# esp32-gps-eth-v9exp.net
KiCad netlist of a schematic drawn in EAGLE
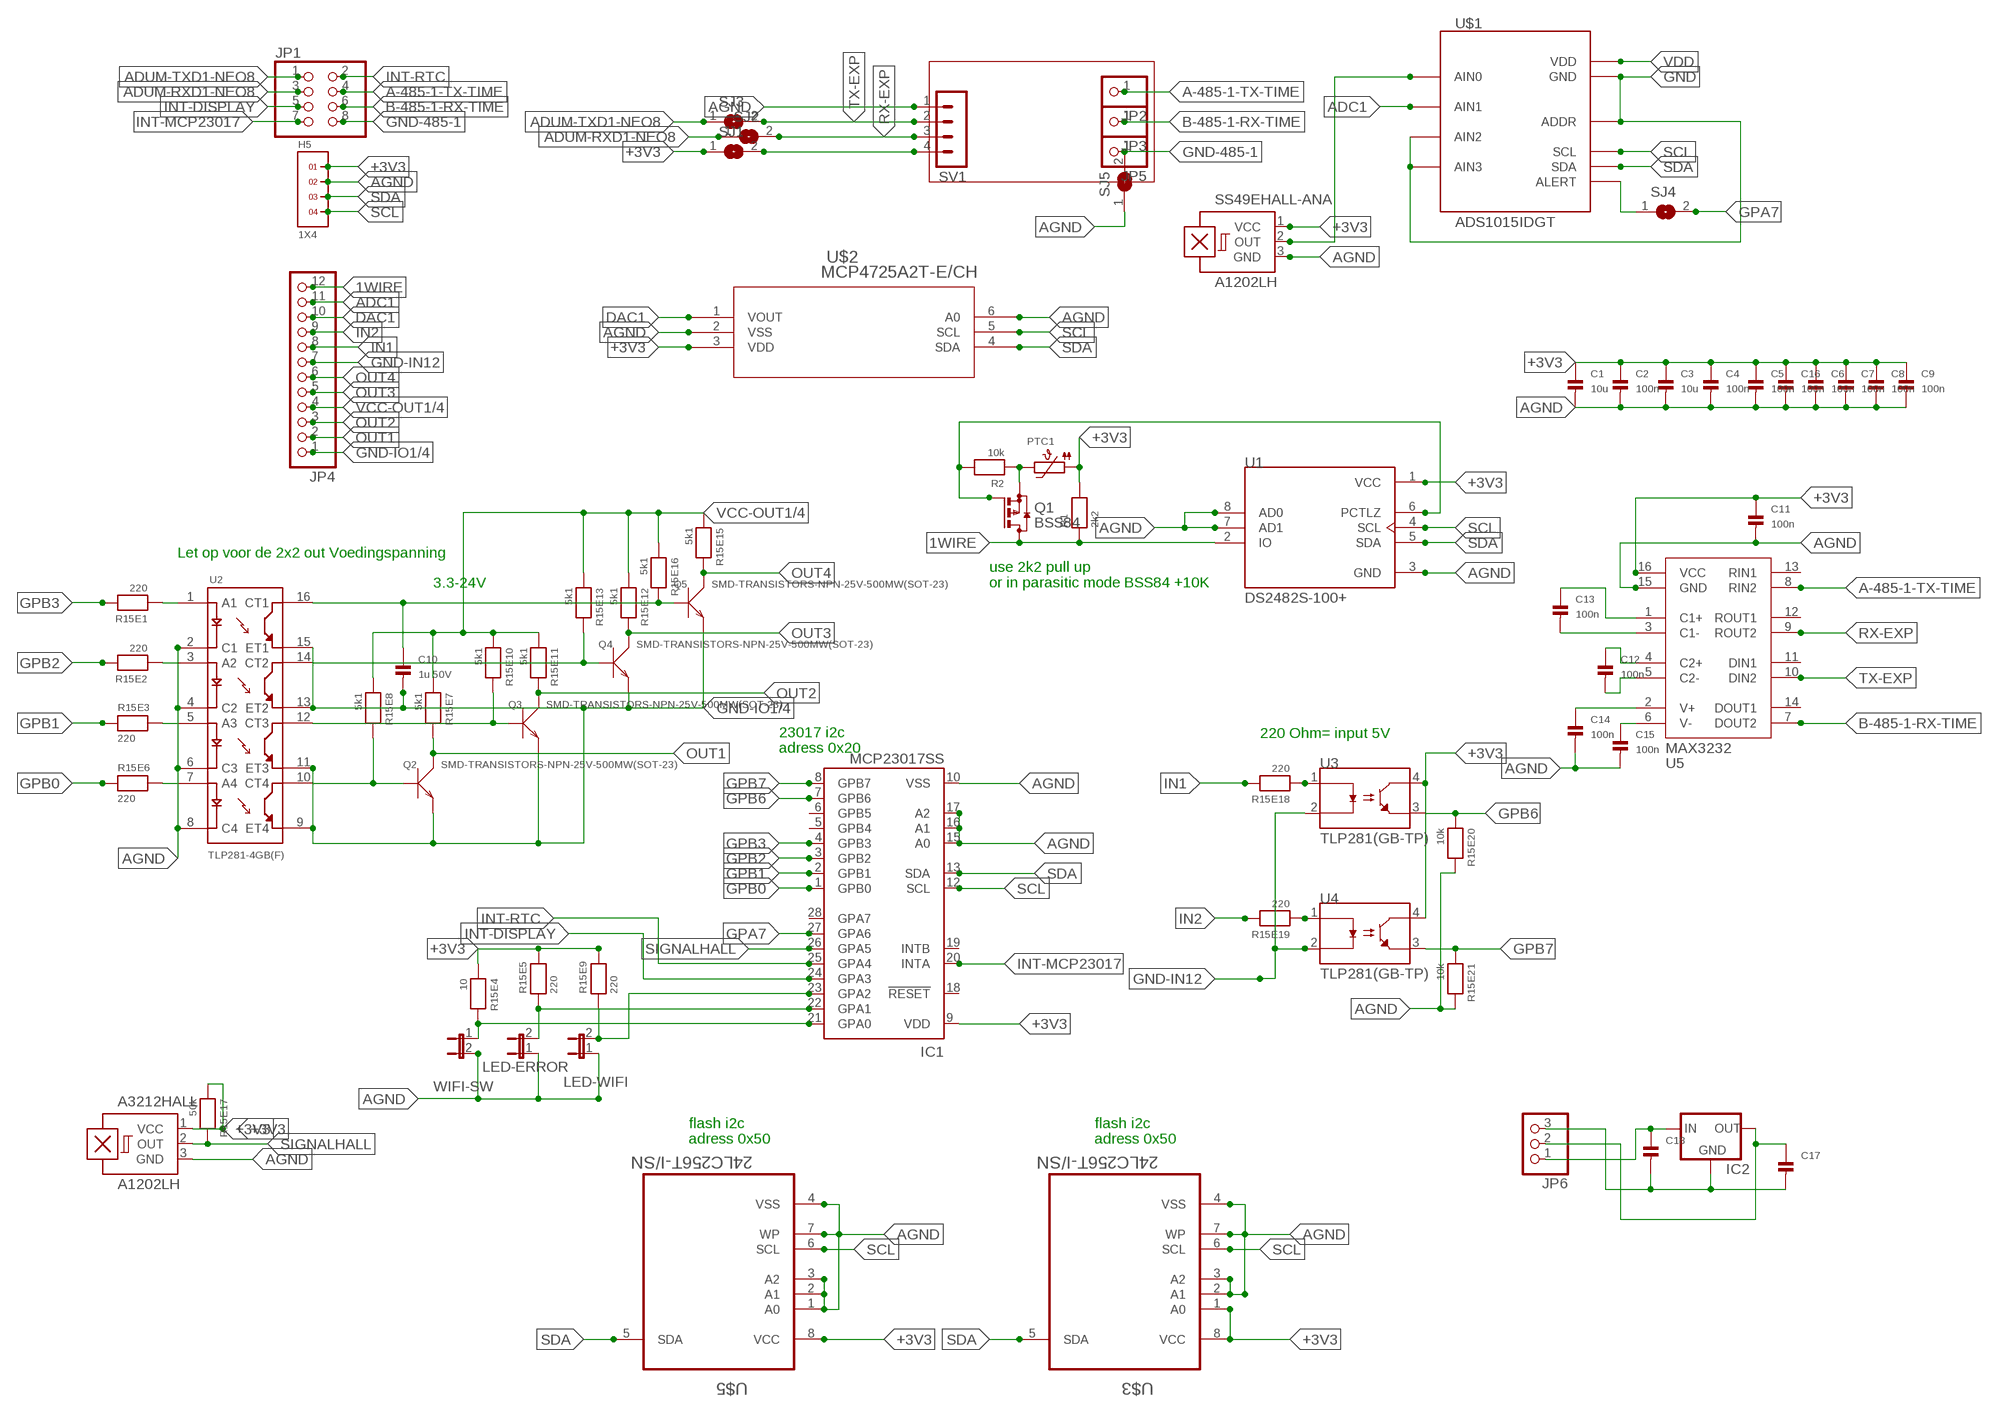
[diagram p0: schematic, sheet 1]

(export (version "E")
  (design (tool "Eeschema 10.0.6"))
  (components
    (comp (ref "A3212HALL")
      (value "A1202LH")
      (footprint "eagle-import:SOT23-W")
      (libsource (lib "eagle-import") (part "A12?LH02"))
    )
    (comp (ref "C1")
      (value "10u")
      (footprint "eagle-import:0805")
      (libsource (lib "eagle-import") (part "CAP_CERAMIC0805"))
    )
    (comp (ref "C2")
      (value "100n")
      (footprint "eagle-import:0805")
      (libsource (lib "eagle-import") (part "CAP_CERAMIC0805"))
    )
    (comp (ref "C3")
      (value "10u")
      (footprint "eagle-import:0805")
      (libsource (lib "eagle-import") (part "CAP_CERAMIC0805"))
    )
    (comp (ref "C4")
      (value "100n")
      (footprint "eagle-import:0805")
      (libsource (lib "eagle-import") (part "CAP_CERAMIC0805"))
    )
    (comp (ref "C5")
      (value "100n")
      (footprint "eagle-import:0805")
      (libsource (lib "eagle-import") (part "CAP_CERAMIC0805"))
    )
    (comp (ref "C6")
      (value "100n")
      (footprint "eagle-import:0805")
      (libsource (lib "eagle-import") (part "CAP_CERAMIC0805"))
    )
    (comp (ref "C7")
      (value "100n")
      (footprint "eagle-import:0805")
      (libsource (lib "eagle-import") (part "CAP_CERAMIC0805"))
    )
    (comp (ref "C8")
      (value "100n")
      (footprint "eagle-import:0805")
      (libsource (lib "eagle-import") (part "CAP_CERAMIC0805"))
    )
    (comp (ref "C9")
      (value "100n")
      (footprint "eagle-import:0805")
      (libsource (lib "eagle-import") (part "CAP_CERAMIC0805"))
    )
    (comp (ref "C10")
      (value "1u 50V")
      (footprint "eagle-import:0805")
      (libsource (lib "eagle-import") (part "CAP_CERAMIC0805"))
    )
    (comp (ref "C11")
      (value "100n")
      (footprint "eagle-import:0805")
      (libsource (lib "eagle-import") (part "CAP_CERAMIC0805"))
    )
    (comp (ref "C12")
      (value "100n")
      (footprint "eagle-import:0805")
      (libsource (lib "eagle-import") (part "CAP_CERAMIC0805"))
    )
    (comp (ref "C13")
      (value "100n")
      (footprint "eagle-import:0805")
      (libsource (lib "eagle-import") (part "CAP_CERAMIC0805"))
    )
    (comp (ref "C14")
      (value "100n")
      (footprint "eagle-import:0805")
      (libsource (lib "eagle-import") (part "CAP_CERAMIC0805"))
    )
    (comp (ref "C15")
      (value "100n")
      (footprint "eagle-import:0805")
      (libsource (lib "eagle-import") (part "CAP_CERAMIC0805"))
    )
    (comp (ref "C16")
      (value "100n")
      (footprint "eagle-import:0805")
      (libsource (lib "eagle-import") (part "CAP_CERAMIC0805"))
    )
    (comp (ref "C17")
      (value "CAP_CERAMIC0805")
      (footprint "eagle-import:0805")
      (libsource (lib "eagle-import") (part "CAP_CERAMIC0805"))
    )
    (comp (ref "C18")
      (value "CAP_CERAMIC0805")
      (footprint "eagle-import:0805")
      (libsource (lib "eagle-import") (part "CAP_CERAMIC0805"))
    )
    (comp (ref "H5")
      (value "1X4")
      (footprint "eagle-import:1X4")
      (libsource (lib "eagle-import") (part "1X4"))
    )
    (comp (ref "IC1")
      (value "MCP23017SS")
      (footprint "eagle-import:SSOP28")
      (fields (field (name "MF") "MICROCHIP") (field (name "MPN") "MCP23017-E/SS"))
      (libsource (lib "eagle-import") (part "MCP23017SS"))
    )
    (comp (ref "IC2")
      (value "LM1117TO263")
      (footprint "eagle-import:TO263")
      (libsource (lib "eagle-import") (part "LM1117TO263"))
    )
    (comp (ref "JP1")
      (value "PINHD-2X4")
      (footprint "eagle-import:2X04")
      (libsource (lib "eagle-import") (part "PINHD-2X4"))
    )
    (comp (ref "JP2")
      (value "PINHD-1X1")
      (footprint "eagle-import:1X01")
      (libsource (lib "eagle-import") (part "PINHD-1X1"))
    )
    (comp (ref "JP3")
      (value "PINHD-1X1")
      (footprint "eagle-import:1X01")
      (libsource (lib "eagle-import") (part "PINHD-1X1"))
    )
    (comp (ref "JP4")
      (value "PINHD-1X12")
      (footprint "eagle-import:1X12")
      (libsource (lib "eagle-import") (part "PINHD-1X12"))
    )
    (comp (ref "JP5")
      (value "PINHD-1X1")
      (footprint "eagle-import:1X01")
      (libsource (lib "eagle-import") (part "PINHD-1X1"))
    )
    (comp (ref "JP6")
      (value "PINHD-1X3")
      (footprint "eagle-import:1X03")
      (libsource (lib "eagle-import") (part "PINHD-1X3"))
    )
    (comp (ref "LED-ERROR")
      (value "JP1E")
      (footprint "eagle-import:JP1")
      (libsource (lib "eagle-import") (part "JP1E"))
    )
    (comp (ref "LED-WIFI")
      (value "JP1E")
      (footprint "eagle-import:JP1")
      (libsource (lib "eagle-import") (part "JP1E"))
    )
    (comp (ref "PTC1")
      (value "PTC1206")
      (footprint "eagle-import:1206")
      (libsource (lib "eagle-import") (part "PTC1206"))
    )
    (comp (ref "Q1")
      (value "BSS84")
      (footprint "eagle-import:SOT23")
      (libsource (lib "eagle-import") (part "BSS84"))
    )
    (comp (ref "Q2")
      (value "SMD-TRANSISTORS-NPN-25V-500MW(SOT-23)")
      (footprint "eagle-import:SOT-23")
      (fields (field (name "MF") "Micro Commercial") (field (name "MP") "S8050"))
      (libsource (lib "eagle-import") (part "SMD-TRANSISTORS-NPN-25V-500MW(SOT-23)"))
    )
    (comp (ref "Q3")
      (value "SMD-TRANSISTORS-NPN-25V-500MW(SOT-23)")
      (footprint "eagle-import:SOT-23")
      (fields (field (name "MF") "Micro Commercial") (field (name "MP") "S8050"))
      (libsource (lib "eagle-import") (part "SMD-TRANSISTORS-NPN-25V-500MW(SOT-23)"))
    )
    (comp (ref "Q4")
      (value "SMD-TRANSISTORS-NPN-25V-500MW(SOT-23)")
      (footprint "eagle-import:SOT-23")
      (fields (field (name "MF") "Micro Commercial") (field (name "MP") "S8050"))
      (libsource (lib "eagle-import") (part "SMD-TRANSISTORS-NPN-25V-500MW(SOT-23)"))
    )
    (comp (ref "Q5")
      (value "SMD-TRANSISTORS-NPN-25V-500MW(SOT-23)")
      (footprint "eagle-import:SOT-23")
      (fields (field (name "MF") "Micro Commercial") (field (name "MP") "S8050"))
      (libsource (lib "eagle-import") (part "SMD-TRANSISTORS-NPN-25V-500MW(SOT-23)"))
    )
    (comp (ref "R1")
      (value "2k2")
      (footprint "eagle-import:0805")
      (libsource (lib "eagle-import") (part "RESISTOR0805"))
    )
    (comp (ref "R2")
      (value "10k")
      (footprint "eagle-import:0805")
      (libsource (lib "eagle-import") (part "RESISTOR0805"))
    )
    (comp (ref "R15E1")
      (value "220")
      (footprint "eagle-import:_0805")
      (libsource (lib "eagle-import") (part "RESISTOR_0805"))
    )
    (comp (ref "R15E2")
      (value "220")
      (footprint "eagle-import:_0805")
      (libsource (lib "eagle-import") (part "RESISTOR_0805"))
    )
    (comp (ref "R15E3")
      (value "220")
      (footprint "eagle-import:_0805")
      (libsource (lib "eagle-import") (part "RESISTOR_0805"))
    )
    (comp (ref "R15E4")
      (value "10")
      (footprint "eagle-import:_0805")
      (libsource (lib "eagle-import") (part "RESISTOR_0805"))
    )
    (comp (ref "R15E5")
      (value "220")
      (footprint "eagle-import:_0805")
      (libsource (lib "eagle-import") (part "RESISTOR_0805"))
    )
    (comp (ref "R15E6")
      (value "220")
      (footprint "eagle-import:_0805")
      (libsource (lib "eagle-import") (part "RESISTOR_0805"))
    )
    (comp (ref "R15E7")
      (value "5k1")
      (footprint "eagle-import:_0805")
      (libsource (lib "eagle-import") (part "RESISTOR_0805"))
    )
    (comp (ref "R15E8")
      (value "5k1")
      (footprint "eagle-import:_0805")
      (libsource (lib "eagle-import") (part "RESISTOR_0805"))
    )
    (comp (ref "R15E9")
      (value "220")
      (footprint "eagle-import:_0805")
      (libsource (lib "eagle-import") (part "RESISTOR_0805"))
    )
    (comp (ref "R15E10")
      (value "5k1")
      (footprint "eagle-import:_0805")
      (libsource (lib "eagle-import") (part "RESISTOR_0805"))
    )
    (comp (ref "R15E11")
      (value "5k1")
      (footprint "eagle-import:_0805")
      (libsource (lib "eagle-import") (part "RESISTOR_0805"))
    )
    (comp (ref "R15E12")
      (value "5k1")
      (footprint "eagle-import:_0805")
      (libsource (lib "eagle-import") (part "RESISTOR_0805"))
    )
    (comp (ref "R15E13")
      (value "5k1")
      (footprint "eagle-import:_0805")
      (libsource (lib "eagle-import") (part "RESISTOR_0805"))
    )
    (comp (ref "R15E15")
      (value "5k1")
      (footprint "eagle-import:_0805")
      (libsource (lib "eagle-import") (part "RESISTOR_0805"))
    )
    (comp (ref "R15E16")
      (value "5k1")
      (footprint "eagle-import:_0805")
      (libsource (lib "eagle-import") (part "RESISTOR_0805"))
    )
    (comp (ref "R15E17")
      (value "50k")
      (footprint "eagle-import:_0805")
      (libsource (lib "eagle-import") (part "RESISTOR_0805"))
    )
    (comp (ref "R15E18")
      (value "220")
      (footprint "eagle-import:_0805")
      (libsource (lib "eagle-import") (part "RESISTOR_0805"))
    )
    (comp (ref "R15E19")
      (value "220")
      (footprint "eagle-import:_0805")
      (libsource (lib "eagle-import") (part "RESISTOR_0805"))
    )
    (comp (ref "R15E20")
      (value "10k")
      (footprint "eagle-import:_0805")
      (libsource (lib "eagle-import") (part "RESISTOR_0805"))
    )
    (comp (ref "R15E21")
      (value "10k")
      (footprint "eagle-import:_0805")
      (libsource (lib "eagle-import") (part "RESISTOR_0805"))
    )
    (comp (ref "SJ1") (value "SJ") (footprint "eagle-import:SJ") (libsource (lib "eagle-import") (part "SJ")))
    (comp (ref "SJ2") (value "SJ") (footprint "eagle-import:SJ") (libsource (lib "eagle-import") (part "SJ")))
    (comp (ref "SJ3") (value "SJ") (footprint "eagle-import:SJ") (libsource (lib "eagle-import") (part "SJ")))
    (comp (ref "SJ4") (value "SJ") (footprint "eagle-import:SJ") (libsource (lib "eagle-import") (part "SJ")))
    (comp (ref "SJ5") (value "SJ") (footprint "eagle-import:SJ") (libsource (lib "eagle-import") (part "SJ")))
    (comp (ref "SS49EHALL-ANA")
      (value "A1202LH")
      (footprint "eagle-import:SOT23-W")
      (libsource (lib "eagle-import") (part "A12?LH02"))
    )
    (comp (ref "SV1")
      (value "MA04-1")
      (footprint "eagle-import:MA04-1")
      (libsource (lib "eagle-import") (part "MA04-1"))
    )
    (comp (ref "U$1")
      (value "ADS1015IDGT")
      (footprint "eagle-import:MSOP10_0.5")
      (fields (field (name "MF") "Texas Instruments") (field (name "MP") "ADS1015"))
      (libsource (lib "eagle-import") (part "ADS1015IDGT"))
    )
    (comp (ref "U$2")
      (value "MCP4725A2T-E/CH")
      (footprint "eagle-import:SOT-23-6_MC")
      (fields (field (name "MF") "Microchip"))
      (libsource (lib "eagle-import") (part "MCP4725A2T-E/CH"))
    )
    (comp (ref "U$3")
      (value "24LC256T-I/SN")
      (footprint "eagle-import:SOIC127P600X175-8N")
      (libsource (lib "eagle-import") (part "24LC256T-I/SN"))
    )
    (comp (ref "U$5")
      (value "24LC256T-I/SN")
      (footprint "eagle-import:SOIC127P600X175-8N")
      (libsource (lib "eagle-import") (part "24LC256T-I/SN"))
    )
    (comp (ref "U1")
      (value "DS2482S-100+")
      (footprint "eagle-import:SOIC127P600X175-8N")
      (fields (field (name "MF") "Maxim Integrated"))
      (libsource (lib "eagle-import") (part "DS2482S-100+"))
    )
    (comp (ref "U2")
      (value "TLP281-4GB(F)")
      (footprint "eagle-import:SOIC127P700X210-16N")
      (fields (field (name "MF") "Toshiba") (field (name "MP") "TLP281-4GB_F_"))
      (libsource (lib "eagle-import") (part "TLP281-4GB(F)"))
    )
    (comp (ref "U3")
      (value "TLP281(GB-TP)")
      (footprint "eagle-import:SOIC127P700X210-4N")
      (fields (field (name "MF") "Toshiba Semiconductor") (field (name "MP") "TLP281_GB-TP_"))
      (libsource (lib "eagle-import") (part "TLP281(GB-TP)"))
    )
    (comp (ref "U4")
      (value "TLP281(GB-TP)")
      (footprint "eagle-import:SOIC127P700X210-4N")
      (fields (field (name "MF") "Toshiba Semiconductor") (field (name "MP") "TLP281_GB-TP_"))
      (libsource (lib "eagle-import") (part "TLP281(GB-TP)"))
    )
    (comp (ref "U5")
      (value "MAX3232")
      (footprint "eagle-import:SO16")
      (fields (field (name "MF") "Texas Instruments"))
      (libsource (lib "eagle-import") (part "MAX3232"))
    )
    (comp (ref "WIFI-SW")
      (value "JP1E")
      (footprint "eagle-import:JP1")
      (libsource (lib "eagle-import") (part "JP1E"))
    )
  )
  (nets
    (net (code "1") (name "+3V3") (class "Default")
      (node (ref "A3212HALL") (pin "1") (pinfunction "VCC_1") (pintype "power_in"))
      (node (ref "C1") (pin "1") (pinfunction "P$1_1") (pintype "passive"))
      (node (ref "C11") (pin "1") (pinfunction "P$1_1") (pintype "passive"))
      (node (ref "C16") (pin "1") (pinfunction "P$1_1") (pintype "passive"))
      (node (ref "C2") (pin "1") (pinfunction "P$1_1") (pintype "passive"))
      (node (ref "C3") (pin "1") (pinfunction "P$1_1") (pintype "passive"))
      (node (ref "C4") (pin "1") (pinfunction "P$1_1") (pintype "passive"))
      (node (ref "C5") (pin "1") (pinfunction "P$1_1") (pintype "passive"))
      (node (ref "C6") (pin "1") (pinfunction "P$1_1") (pintype "passive"))
      (node (ref "C7") (pin "1") (pinfunction "P$1_1") (pintype "passive"))
      (node (ref "C8") (pin "1") (pinfunction "P$1_1") (pintype "passive"))
      (node (ref "C9") (pin "1") (pinfunction "P$1_1") (pintype "passive"))
      (node (ref "H5") (pin "1") (pinfunction "1_1") (pintype "bidirectional"))
      (node (ref "IC1") (pin "9") (pinfunction "VDD_9") (pintype "power_in"))
      (node (ref "PTC1") (pin "1") (pinfunction "1_1") (pintype "passive"))
      (node (ref "R1") (pin "2") (pinfunction "2_2") (pintype "passive"))
      (node (ref "R15E17") (pin "1") (pinfunction "1_1") (pintype "passive"))
      (node (ref "R15E4") (pin "1") (pinfunction "1_1") (pintype "passive"))
      (node (ref "R15E5") (pin "2") (pinfunction "2_2") (pintype "passive"))
      (node (ref "R15E9") (pin "2") (pinfunction "2_2") (pintype "passive"))
      (node (ref "SJ1") (pin "1") (pinfunction "1_1") (pintype "passive"))
      (node (ref "SS49EHALL-ANA") (pin "1") (pinfunction "VCC_1") (pintype "power_in"))
      (node (ref "U$2") (pin "3") (pinfunction "VDD_3") (pintype "passive"))
      (node (ref "U$3") (pin "1") (pinfunction "A0_1") (pintype "input"))
      (node (ref "U$3") (pin "8") (pinfunction "VCC_8") (pintype "power_in"))
      (node (ref "U$5") (pin "8") (pinfunction "VCC_8") (pintype "power_in"))
      (node (ref "U1") (pin "1") (pinfunction "VCC_1") (pintype "power_in"))
      (node (ref "U3") (pin "4") (pinfunction "COLLECTOR_4") (pintype "passive"))
      (node (ref "U4") (pin "4") (pinfunction "COLLECTOR_4") (pintype "passive"))
      (node (ref "U5") (pin "16") (pinfunction "VCC_16") (pintype "passive"))
    )
    (net (code "2") (name "1WIRE") (class "Default")
      (node (ref "JP4") (pin "12") (pinfunction "12_12") (pintype "passive"))
      (node (ref "Q1") (pin "3") (pinfunction "D_3") (pintype "passive"))
      (node (ref "R1") (pin "1") (pinfunction "1_1") (pintype "passive"))
      (node (ref "U1") (pin "2") (pinfunction "IO_2") (pintype "bidirectional"))
    )
    (net (code "3") (name "A-485-1-TX-TIME") (class "Default")
      (node (ref "JP1") (pin "4") (pinfunction "4_4") (pintype "passive"))
      (node (ref "JP2") (pin "1") (pinfunction "1_1") (pintype "passive"))
      (node (ref "U5") (pin "8") (pinfunction "RIN2_8") (pintype "input"))
    )
    (net (code "4") (name "ADC1") (class "Default")
      (node (ref "JP4") (pin "11") (pinfunction "11_11") (pintype "passive"))
      (node (ref "U$1") (pin "5") (pinfunction "AIN1_5") (pintype "input"))
    )
    (net (code "5") (name "ADUM-RXD1-NEO8") (class "Default")
      (node (ref "JP1") (pin "3") (pinfunction "3_3") (pintype "passive"))
      (node (ref "SJ2") (pin "1") (pinfunction "1_1") (pintype "passive"))
    )
    (net (code "6") (name "ADUM-TXD1-NEO8") (class "Default")
      (node (ref "JP1") (pin "1") (pinfunction "1_1") (pintype "passive"))
      (node (ref "SJ3") (pin "1") (pinfunction "1_1") (pintype "passive"))
    )
    (net (code "7") (name "AGND") (class "Default")
      (node (ref "A3212HALL") (pin "3") (pinfunction "GND_3") (pintype "power_in"))
      (node (ref "C1") (pin "2") (pinfunction "P$2_2") (pintype "passive"))
      (node (ref "C11") (pin "2") (pinfunction "P$2_2") (pintype "passive"))
      (node (ref "C14") (pin "2") (pinfunction "P$2_2") (pintype "passive"))
      (node (ref "C15") (pin "2") (pinfunction "P$2_2") (pintype "passive"))
      (node (ref "C16") (pin "2") (pinfunction "P$2_2") (pintype "passive"))
      (node (ref "C2") (pin "2") (pinfunction "P$2_2") (pintype "passive"))
      (node (ref "C3") (pin "2") (pinfunction "P$2_2") (pintype "passive"))
      (node (ref "C4") (pin "2") (pinfunction "P$2_2") (pintype "passive"))
      (node (ref "C5") (pin "2") (pinfunction "P$2_2") (pintype "passive"))
      (node (ref "C6") (pin "2") (pinfunction "P$2_2") (pintype "passive"))
      (node (ref "C7") (pin "2") (pinfunction "P$2_2") (pintype "passive"))
      (node (ref "C8") (pin "2") (pinfunction "P$2_2") (pintype "passive"))
      (node (ref "C9") (pin "2") (pinfunction "P$2_2") (pintype "passive"))
      (node (ref "H5") (pin "2") (pinfunction "2_2") (pintype "bidirectional"))
      (node (ref "IC1") (pin "10") (pinfunction "VSS_10") (pintype "power_in"))
      (node (ref "IC1") (pin "15") (pinfunction "A0_15") (pintype "input"))
      (node (ref "IC1") (pin "16") (pinfunction "A1_16") (pintype "input"))
      (node (ref "IC1") (pin "17") (pinfunction "A2_17") (pintype "input"))
      (node (ref "LED-ERROR") (pin "1") (pinfunction "1_1") (pintype "passive"))
      (node (ref "LED-WIFI") (pin "1") (pinfunction "1_1") (pintype "passive"))
      (node (ref "R15E20") (pin "2") (pinfunction "2_2") (pintype "passive"))
      (node (ref "R15E21") (pin "2") (pinfunction "2_2") (pintype "passive"))
      (node (ref "SJ5") (pin "1") (pinfunction "1_1") (pintype "passive"))
      (node (ref "SS49EHALL-ANA") (pin "3") (pinfunction "GND_3") (pintype "power_in"))
      (node (ref "SV1") (pin "1") (pinfunction "1_1") (pintype "passive"))
      (node (ref "U$2") (pin "2") (pinfunction "VSS_2") (pintype "passive"))
      (node (ref "U$2") (pin "6") (pinfunction "A0_6") (pintype "passive"))
      (node (ref "U$3") (pin "2") (pinfunction "A1_2") (pintype "input"))
      (node (ref "U$3") (pin "3") (pinfunction "A2_3") (pintype "input"))
      (node (ref "U$3") (pin "4") (pinfunction "VSS_4") (pintype "passive"))
      (node (ref "U$3") (pin "7") (pinfunction "WP_7") (pintype "input"))
      (node (ref "U$5") (pin "1") (pinfunction "A0_1") (pintype "input"))
      (node (ref "U$5") (pin "2") (pinfunction "A1_2") (pintype "input"))
      (node (ref "U$5") (pin "3") (pinfunction "A2_3") (pintype "input"))
      (node (ref "U$5") (pin "4") (pinfunction "VSS_4") (pintype "passive"))
      (node (ref "U$5") (pin "7") (pinfunction "WP_7") (pintype "input"))
      (node (ref "U1") (pin "3") (pinfunction "GND_3") (pintype "power_in"))
      (node (ref "U1") (pin "7") (pinfunction "AD1_7") (pintype "input"))
      (node (ref "U1") (pin "8") (pinfunction "AD0_8") (pintype "input"))
      (node (ref "U2") (pin "2") (pinfunction "C1_2") (pintype "passive"))
      (node (ref "U2") (pin "4") (pinfunction "C2_4") (pintype "passive"))
      (node (ref "U2") (pin "6") (pinfunction "C3_6") (pintype "passive"))
      (node (ref "U2") (pin "8") (pinfunction "C4_8") (pintype "passive"))
      (node (ref "U5") (pin "15") (pinfunction "GND_15") (pintype "passive"))
      (node (ref "WIFI-SW") (pin "2") (pinfunction "2_2") (pintype "passive"))
    )
    (net (code "8") (name "B-485-1-RX-TIME") (class "Default")
      (node (ref "JP1") (pin "6") (pinfunction "6_6") (pintype "passive"))
      (node (ref "JP3") (pin "1") (pinfunction "1_1") (pintype "passive"))
      (node (ref "U5") (pin "7") (pinfunction "DOUT2_7") (pintype "output"))
    )
    (net (code "9") (name "DAC1") (class "Default")
      (node (ref "JP4") (pin "10") (pinfunction "10_10") (pintype "passive"))
      (node (ref "U$2") (pin "1") (pinfunction "VOUT_1") (pintype "passive"))
    )
    (net (code "10") (name "GND") (class "Default")
      (node (ref "U$1") (pin "1") (pinfunction "ADDR_1") (pintype "input"))
      (node (ref "U$1") (pin "3") (pinfunction "GND_3") (pintype "power_in"))
      (node (ref "U$1") (pin "6") (pinfunction "AIN2_6") (pintype "input"))
      (node (ref "U$1") (pin "7") (pinfunction "AIN3_7") (pintype "input"))
    )
    (net (code "11") (name "GND-485-1") (class "Default")
      (node (ref "JP1") (pin "8") (pinfunction "8_8") (pintype "passive"))
      (node (ref "JP5") (pin "1") (pinfunction "1_1") (pintype "passive"))
      (node (ref "SJ5") (pin "2") (pinfunction "2_2") (pintype "passive"))
    )
    (net (code "12") (name "GND-IN12") (class "Default")
      (node (ref "JP4") (pin "7") (pinfunction "7_7") (pintype "passive"))
      (node (ref "U3") (pin "2") (pinfunction "CATHODE_2") (pintype "passive"))
      (node (ref "U4") (pin "2") (pinfunction "CATHODE_2") (pintype "passive"))
    )
    (net (code "13") (name "GND-IO1{slash}4") (class "Default")
      (node (ref "C10") (pin "2") (pinfunction "P$2_2") (pintype "passive"))
      (node (ref "JP4") (pin "1") (pinfunction "1_1") (pintype "passive"))
      (node (ref "Q2") (pin "2") (pinfunction "E_2") (pintype "passive"))
      (node (ref "Q3") (pin "2") (pinfunction "E_2") (pintype "passive"))
      (node (ref "Q4") (pin "2") (pinfunction "E_2") (pintype "passive"))
      (node (ref "Q5") (pin "2") (pinfunction "E_2") (pintype "passive"))
      (node (ref "U2") (pin "11") (pinfunction "ET3_11") (pintype "passive"))
      (node (ref "U2") (pin "13") (pinfunction "ET2_13") (pintype "passive"))
      (node (ref "U2") (pin "15") (pinfunction "ET1_15") (pintype "passive"))
      (node (ref "U2") (pin "9") (pinfunction "ET4_9") (pintype "passive"))
    )
    (net (code "14") (name "GPA7") (class "Default")
      (node (ref "IC1") (pin "27") (pinfunction "GPA6_27") (pintype "bidirectional"))
      (node (ref "SJ4") (pin "2") (pinfunction "2_2") (pintype "passive"))
    )
    (net (code "15") (name "GPB0") (class "Default")
      (node (ref "IC1") (pin "1") (pinfunction "GPB0_1") (pintype "bidirectional"))
      (node (ref "R15E6") (pin "1") (pinfunction "1_1") (pintype "passive"))
    )
    (net (code "16") (name "GPB1") (class "Default")
      (node (ref "IC1") (pin "2") (pinfunction "GPB1_2") (pintype "bidirectional"))
      (node (ref "R15E3") (pin "1") (pinfunction "1_1") (pintype "passive"))
    )
    (net (code "17") (name "GPB2") (class "Default")
      (node (ref "IC1") (pin "3") (pinfunction "GPB2_3") (pintype "bidirectional"))
      (node (ref "R15E2") (pin "2") (pinfunction "2_2") (pintype "passive"))
    )
    (net (code "18") (name "GPB3") (class "Default")
      (node (ref "IC1") (pin "4") (pinfunction "GPB3_4") (pintype "bidirectional"))
      (node (ref "R15E1") (pin "2") (pinfunction "2_2") (pintype "passive"))
    )
    (net (code "19") (name "GPB6") (class "Default")
      (node (ref "IC1") (pin "7") (pinfunction "GPB6_7") (pintype "bidirectional"))
      (node (ref "R15E20") (pin "1") (pinfunction "1_1") (pintype "passive"))
      (node (ref "U3") (pin "3") (pinfunction "EMITTER_3") (pintype "passive"))
    )
    (net (code "20") (name "GPB7") (class "Default")
      (node (ref "IC1") (pin "8") (pinfunction "GPB7_8") (pintype "bidirectional"))
      (node (ref "R15E21") (pin "1") (pinfunction "1_1") (pintype "passive"))
      (node (ref "U4") (pin "3") (pinfunction "EMITTER_3") (pintype "passive"))
    )
    (net (code "21") (name "IN1") (class "Default")
      (node (ref "JP4") (pin "8") (pinfunction "8_8") (pintype "passive"))
      (node (ref "R15E18") (pin "2") (pinfunction "2_2") (pintype "passive"))
    )
    (net (code "22") (name "IN2") (class "Default")
      (node (ref "JP4") (pin "9") (pinfunction "9_9") (pintype "passive"))
      (node (ref "R15E19") (pin "2") (pinfunction "2_2") (pintype "passive"))
    )
    (net (code "23") (name "INT-DISPLAY") (class "Default")
      (node (ref "IC1") (pin "24") (pinfunction "GPA3_24") (pintype "bidirectional"))
      (node (ref "JP1") (pin "5") (pinfunction "5_5") (pintype "passive"))
    )
    (net (code "24") (name "INT-MCP23017") (class "Default")
      (node (ref "IC1") (pin "20") (pinfunction "INTA_20") (pintype "output"))
      (node (ref "JP1") (pin "7") (pinfunction "7_7") (pintype "passive"))
    )
    (net (code "25") (name "INT-RTC") (class "Default")
      (node (ref "IC1") (pin "25") (pinfunction "GPA4_25") (pintype "bidirectional"))
      (node (ref "JP1") (pin "2") (pinfunction "2_2") (pintype "passive"))
    )
    (net (code "26") (name "Net-(C10-P$1)") (class "Default")
      (node (ref "C10") (pin "1") (pinfunction "P$1_1") (pintype "passive"))
      (node (ref "Q5") (pin "1") (pinfunction "B_1") (pintype "passive"))
      (node (ref "R15E16") (pin "2") (pinfunction "2_2") (pintype "passive"))
      (node (ref "U2") (pin "16") (pinfunction "CT1_16") (pintype "passive"))
    )
    (net (code "27") (name "Net-(C12-P$1)") (class "Default")
      (node (ref "C12") (pin "1") (pinfunction "P$1_1") (pintype "passive"))
      (node (ref "U5") (pin "4") (pinfunction "C2+_4") (pintype "passive"))
    )
    (net (code "28") (name "Net-(C12-P$2)") (class "Default")
      (node (ref "C12") (pin "2") (pinfunction "P$2_2") (pintype "passive"))
      (node (ref "U5") (pin "5") (pinfunction "C2-_5") (pintype "passive"))
    )
    (net (code "29") (name "Net-(C13-P$1)") (class "Default")
      (node (ref "C13") (pin "1") (pinfunction "P$1_1") (pintype "passive"))
      (node (ref "U5") (pin "1") (pinfunction "C1+_1") (pintype "passive"))
    )
    (net (code "30") (name "Net-(C13-P$2)") (class "Default")
      (node (ref "C13") (pin "2") (pinfunction "P$2_2") (pintype "passive"))
      (node (ref "U5") (pin "3") (pinfunction "C1-_3") (pintype "passive"))
    )
    (net (code "31") (name "Net-(C14-P$1)") (class "Default")
      (node (ref "C14") (pin "1") (pinfunction "P$1_1") (pintype "passive"))
      (node (ref "U5") (pin "2") (pinfunction "V+_2") (pintype "output"))
    )
    (net (code "32") (name "Net-(C15-P$1)") (class "Default")
      (node (ref "C15") (pin "1") (pinfunction "P$1_1") (pintype "passive"))
      (node (ref "U5") (pin "6") (pinfunction "V-_6") (pintype "output"))
    )
    (net (code "33") (name "Net-(C17-P$1)") (class "Default")
      (node (ref "C17") (pin "1") (pinfunction "P$1_1") (pintype "passive"))
      (node (ref "IC2") (pin "2") (pinfunction "OUT_2") (pintype "passive"))
      (node (ref "JP6") (pin "2") (pinfunction "2_2") (pintype "passive"))
    )
    (net (code "34") (name "Net-(C17-P$2)") (class "Default")
      (node (ref "C17") (pin "2") (pinfunction "P$2_2") (pintype "passive"))
      (node (ref "C18") (pin "2") (pinfunction "P$2_2") (pintype "passive"))
      (node (ref "IC2") (pin "1") (pinfunction "GND_1") (pintype "input"))
      (node (ref "JP6") (pin "3") (pinfunction "3_3") (pintype "passive"))
    )
    (net (code "35") (name "Net-(C18-P$1)") (class "Default")
      (node (ref "C18") (pin "1") (pinfunction "P$1_1") (pintype "passive"))
      (node (ref "IC2") (pin "3") (pinfunction "IN_3") (pintype "input"))
      (node (ref "JP6") (pin "1") (pinfunction "1_1") (pintype "passive"))
    )
    (net (code "36") (name "Net-(IC1-GPA0)") (class "Default")
      (node (ref "IC1") (pin "21") (pinfunction "GPA0_21") (pintype "bidirectional"))
      (node (ref "R15E4") (pin "2") (pinfunction "2_2") (pintype "passive"))
      (node (ref "WIFI-SW") (pin "1") (pinfunction "1_1") (pintype "passive"))
    )
    (net (code "37") (name "Net-(IC1-GPA1)") (class "Default")
      (node (ref "IC1") (pin "22") (pinfunction "GPA1_22") (pintype "bidirectional"))
      (node (ref "LED-ERROR") (pin "2") (pinfunction "2_2") (pintype "passive"))
      (node (ref "R15E5") (pin "1") (pinfunction "1_1") (pintype "passive"))
    )
    (net (code "38") (name "Net-(IC1-GPA2)") (class "Default")
      (node (ref "IC1") (pin "23") (pinfunction "GPA2_23") (pintype "bidirectional"))
      (node (ref "LED-WIFI") (pin "2") (pinfunction "2_2") (pintype "passive"))
      (node (ref "R15E9") (pin "1") (pinfunction "1_1") (pintype "passive"))
    )
    (net (code "39") (name "Net-(Q1-G)") (class "Default")
      (node (ref "Q1") (pin "1") (pinfunction "G_1") (pintype "passive"))
      (node (ref "R2") (pin "2") (pinfunction "2_2") (pintype "passive"))
      (node (ref "U1") (pin "6") (pinfunction "PCTLZ_6") (pintype "output"))
    )
    (net (code "40") (name "Net-(Q1-S)") (class "Default")
      (node (ref "PTC1") (pin "2") (pinfunction "2_2") (pintype "passive"))
      (node (ref "Q1") (pin "2") (pinfunction "S_2") (pintype "passive"))
      (node (ref "R2") (pin "1") (pinfunction "1_1") (pintype "passive"))
    )
    (net (code "41") (name "Net-(Q2-B)") (class "Default")
      (node (ref "Q2") (pin "1") (pinfunction "B_1") (pintype "passive"))
      (node (ref "R15E8") (pin "2") (pinfunction "2_2") (pintype "passive"))
      (node (ref "U2") (pin "10") (pinfunction "CT4_10") (pintype "passive"))
    )
    (net (code "42") (name "Net-(Q3-B)") (class "Default")
      (node (ref "Q3") (pin "1") (pinfunction "B_1") (pintype "passive"))
      (node (ref "R15E10") (pin "2") (pinfunction "2_2") (pintype "passive"))
      (node (ref "U2") (pin "12") (pinfunction "CT3_12") (pintype "passive"))
    )
    (net (code "43") (name "Net-(Q4-B)") (class "Default")
      (node (ref "Q4") (pin "1") (pinfunction "B_1") (pintype "passive"))
      (node (ref "R15E13") (pin "2") (pinfunction "2_2") (pintype "passive"))
      (node (ref "U2") (pin "14") (pinfunction "CT2_14") (pintype "passive"))
    )
    (net (code "44") (name "Net-(SJ1-Pad2)") (class "Default")
      (node (ref "SJ1") (pin "2") (pinfunction "2_2") (pintype "passive"))
      (node (ref "SV1") (pin "4") (pinfunction "4_4") (pintype "passive"))
    )
    (net (code "45") (name "Net-(SS49EHALL-ANA-OUT)") (class "Default")
      (node (ref "SS49EHALL-ANA") (pin "2") (pinfunction "OUT_2") (pintype "output"))
      (node (ref "U$1") (pin "4") (pinfunction "AIN0_4") (pintype "input"))
    )
    (net (code "46") (name "Net-(U$1-ALERT)") (class "Default")
      (node (ref "SJ4") (pin "1") (pinfunction "1_1") (pintype "passive"))
      (node (ref "U$1") (pin "2") (pinfunction "ALERT_2") (pintype "output"))
    )
    (net (code "47") (name "Net-(U2-A1)") (class "Default")
      (node (ref "R15E1") (pin "1") (pinfunction "1_1") (pintype "passive"))
      (node (ref "U2") (pin "1") (pinfunction "A1_1") (pintype "passive"))
    )
    (net (code "48") (name "Net-(U2-A2)") (class "Default")
      (node (ref "R15E2") (pin "1") (pinfunction "1_1") (pintype "passive"))
      (node (ref "U2") (pin "3") (pinfunction "A2_3") (pintype "passive"))
    )
    (net (code "49") (name "Net-(U2-A3)") (class "Default")
      (node (ref "R15E3") (pin "2") (pinfunction "2_2") (pintype "passive"))
      (node (ref "U2") (pin "5") (pinfunction "A3_5") (pintype "passive"))
    )
    (net (code "50") (name "Net-(U2-A4)") (class "Default")
      (node (ref "R15E6") (pin "2") (pinfunction "2_2") (pintype "passive"))
      (node (ref "U2") (pin "7") (pinfunction "A4_7") (pintype "passive"))
    )
    (net (code "51") (name "Net-(U3-ANODE)") (class "Default")
      (node (ref "R15E18") (pin "1") (pinfunction "1_1") (pintype "passive"))
      (node (ref "U3") (pin "1") (pinfunction "ANODE_1") (pintype "passive"))
    )
    (net (code "52") (name "Net-(U4-ANODE)") (class "Default")
      (node (ref "R15E19") (pin "1") (pinfunction "1_1") (pintype "passive"))
      (node (ref "U4") (pin "1") (pinfunction "ANODE_1") (pintype "passive"))
    )
    (net (code "53") (name "OUT1") (class "Default")
      (node (ref "JP4") (pin "2") (pinfunction "2_2") (pintype "passive"))
      (node (ref "Q2") (pin "3") (pinfunction "C_3") (pintype "passive"))
      (node (ref "R15E7") (pin "2") (pinfunction "2_2") (pintype "passive"))
    )
    (net (code "54") (name "OUT2") (class "Default")
      (node (ref "JP4") (pin "3") (pinfunction "3_3") (pintype "passive"))
      (node (ref "Q3") (pin "3") (pinfunction "C_3") (pintype "passive"))
      (node (ref "R15E11") (pin "2") (pinfunction "2_2") (pintype "passive"))
    )
    (net (code "55") (name "OUT3") (class "Default")
      (node (ref "JP4") (pin "5") (pinfunction "5_5") (pintype "passive"))
      (node (ref "Q4") (pin "3") (pinfunction "C_3") (pintype "passive"))
      (node (ref "R15E12") (pin "2") (pinfunction "2_2") (pintype "passive"))
    )
    (net (code "56") (name "OUT4") (class "Default")
      (node (ref "JP4") (pin "6") (pinfunction "6_6") (pintype "passive"))
      (node (ref "Q5") (pin "3") (pinfunction "C_3") (pintype "passive"))
      (node (ref "R15E15") (pin "2") (pinfunction "2_2") (pintype "passive"))
    )
    (net (code "57") (name "RX-EXP") (class "Default")
      (node (ref "SJ2") (pin "2") (pinfunction "2_2") (pintype "passive"))
      (node (ref "SV1") (pin "3") (pinfunction "3_3") (pintype "passive"))
      (node (ref "U5") (pin "9") (pinfunction "ROUT2_9") (pintype "output"))
    )
    (net (code "58") (name "SCL") (class "Default")
      (node (ref "H5") (pin "4") (pinfunction "4_4") (pintype "bidirectional"))
      (node (ref "IC1") (pin "12") (pinfunction "SCL_12") (pintype "input"))
      (node (ref "U$1") (pin "10") (pinfunction "SCL_10") (pintype "bidirectional"))
      (node (ref "U$2") (pin "5") (pinfunction "SCL_5") (pintype "passive"))
      (node (ref "U$3") (pin "6") (pinfunction "SCL_6") (pintype "input"))
      (node (ref "U$5") (pin "6") (pinfunction "SCL_6") (pintype "input"))
      (node (ref "U1") (pin "4") (pinfunction "SCL_4") (pintype "input"))
    )
    (net (code "59") (name "SDA") (class "Default")
      (node (ref "H5") (pin "3") (pinfunction "3_3") (pintype "bidirectional"))
      (node (ref "IC1") (pin "13") (pinfunction "SDA_13") (pintype "bidirectional"))
      (node (ref "U$1") (pin "9") (pinfunction "SDA_9") (pintype "bidirectional"))
      (node (ref "U$2") (pin "4") (pinfunction "SDA_4") (pintype "passive"))
      (node (ref "U$3") (pin "5") (pinfunction "SDA_5") (pintype "bidirectional"))
      (node (ref "U$5") (pin "5") (pinfunction "SDA_5") (pintype "bidirectional"))
      (node (ref "U1") (pin "5") (pinfunction "SDA_5") (pintype "bidirectional"))
    )
    (net (code "60") (name "SIGNALHALL") (class "Default")
      (node (ref "A3212HALL") (pin "2") (pinfunction "OUT_2") (pintype "output"))
      (node (ref "IC1") (pin "26") (pinfunction "GPA5_26") (pintype "bidirectional"))
      (node (ref "R15E17") (pin "2") (pinfunction "2_2") (pintype "passive"))
    )
    (net (code "61") (name "TX-EXP") (class "Default")
      (node (ref "SJ3") (pin "2") (pinfunction "2_2") (pintype "passive"))
      (node (ref "SV1") (pin "2") (pinfunction "2_2") (pintype "passive"))
      (node (ref "U5") (pin "10") (pinfunction "DIN2_10") (pintype "input"))
    )
    (net (code "62") (name "VCC-OUT1{slash}4") (class "Default")
      (node (ref "JP4") (pin "4") (pinfunction "4_4") (pintype "passive"))
      (node (ref "R15E10") (pin "1") (pinfunction "1_1") (pintype "passive"))
      (node (ref "R15E11") (pin "1") (pinfunction "1_1") (pintype "passive"))
      (node (ref "R15E12") (pin "1") (pinfunction "1_1") (pintype "passive"))
      (node (ref "R15E13") (pin "1") (pinfunction "1_1") (pintype "passive"))
      (node (ref "R15E15") (pin "1") (pinfunction "1_1") (pintype "passive"))
      (node (ref "R15E16") (pin "1") (pinfunction "1_1") (pintype "passive"))
      (node (ref "R15E7") (pin "1") (pinfunction "1_1") (pintype "passive"))
      (node (ref "R15E8") (pin "1") (pinfunction "1_1") (pintype "passive"))
    )
    (net (code "63") (name "VDD") (class "Default")
      (node (ref "U$1") (pin "8") (pinfunction "VDD_8") (pintype "power_in"))
    )
    (net (code "64") (name "unconnected-(IC1-GPA7-Pad28)") (class "Default")
      (node (ref "IC1") (pin "28") (pinfunction "GPA7_28") (pintype "bidirectional"))
    )
    (net (code "65") (name "unconnected-(IC1-GPB4-Pad5)") (class "Default")
      (node (ref "IC1") (pin "5") (pinfunction "GPB4_5") (pintype "bidirectional"))
    )
    (net (code "66") (name "unconnected-(IC1-GPB5-Pad6)") (class "Default")
      (node (ref "IC1") (pin "6") (pinfunction "GPB5_6") (pintype "bidirectional"))
    )
    (net (code "67") (name "unconnected-(IC1-INTB-Pad19)") (class "Default")
      (node (ref "IC1") (pin "19") (pinfunction "INTB_19") (pintype "output"))
    )
    (net (code "68") (name "unconnected-(IC1-~{RESET}-Pad18)") (class "Default")
      (node (ref "IC1") (pin "18") (pinfunction "~{RESET}_18") (pintype "input"))
    )
    (net (code "69") (name "unconnected-(U5-DIN1-Pad11)") (class "Default")
      (node (ref "U5") (pin "11") (pinfunction "DIN1_11") (pintype "input"))
    )
    (net (code "70") (name "unconnected-(U5-DOUT1-Pad14)") (class "Default")
      (node (ref "U5") (pin "14") (pinfunction "DOUT1_14") (pintype "output"))
    )
    (net (code "71") (name "unconnected-(U5-RIN1-Pad13)") (class "Default")
      (node (ref "U5") (pin "13") (pinfunction "RIN1_13") (pintype "input"))
    )
    (net (code "72") (name "unconnected-(U5-ROUT1-Pad12)") (class "Default")
      (node (ref "U5") (pin "12") (pinfunction "ROUT1_12") (pintype "output"))
    )
  )
)
